# arduinoShield.net
KiCad netlist of a schematic drawn in EAGLE
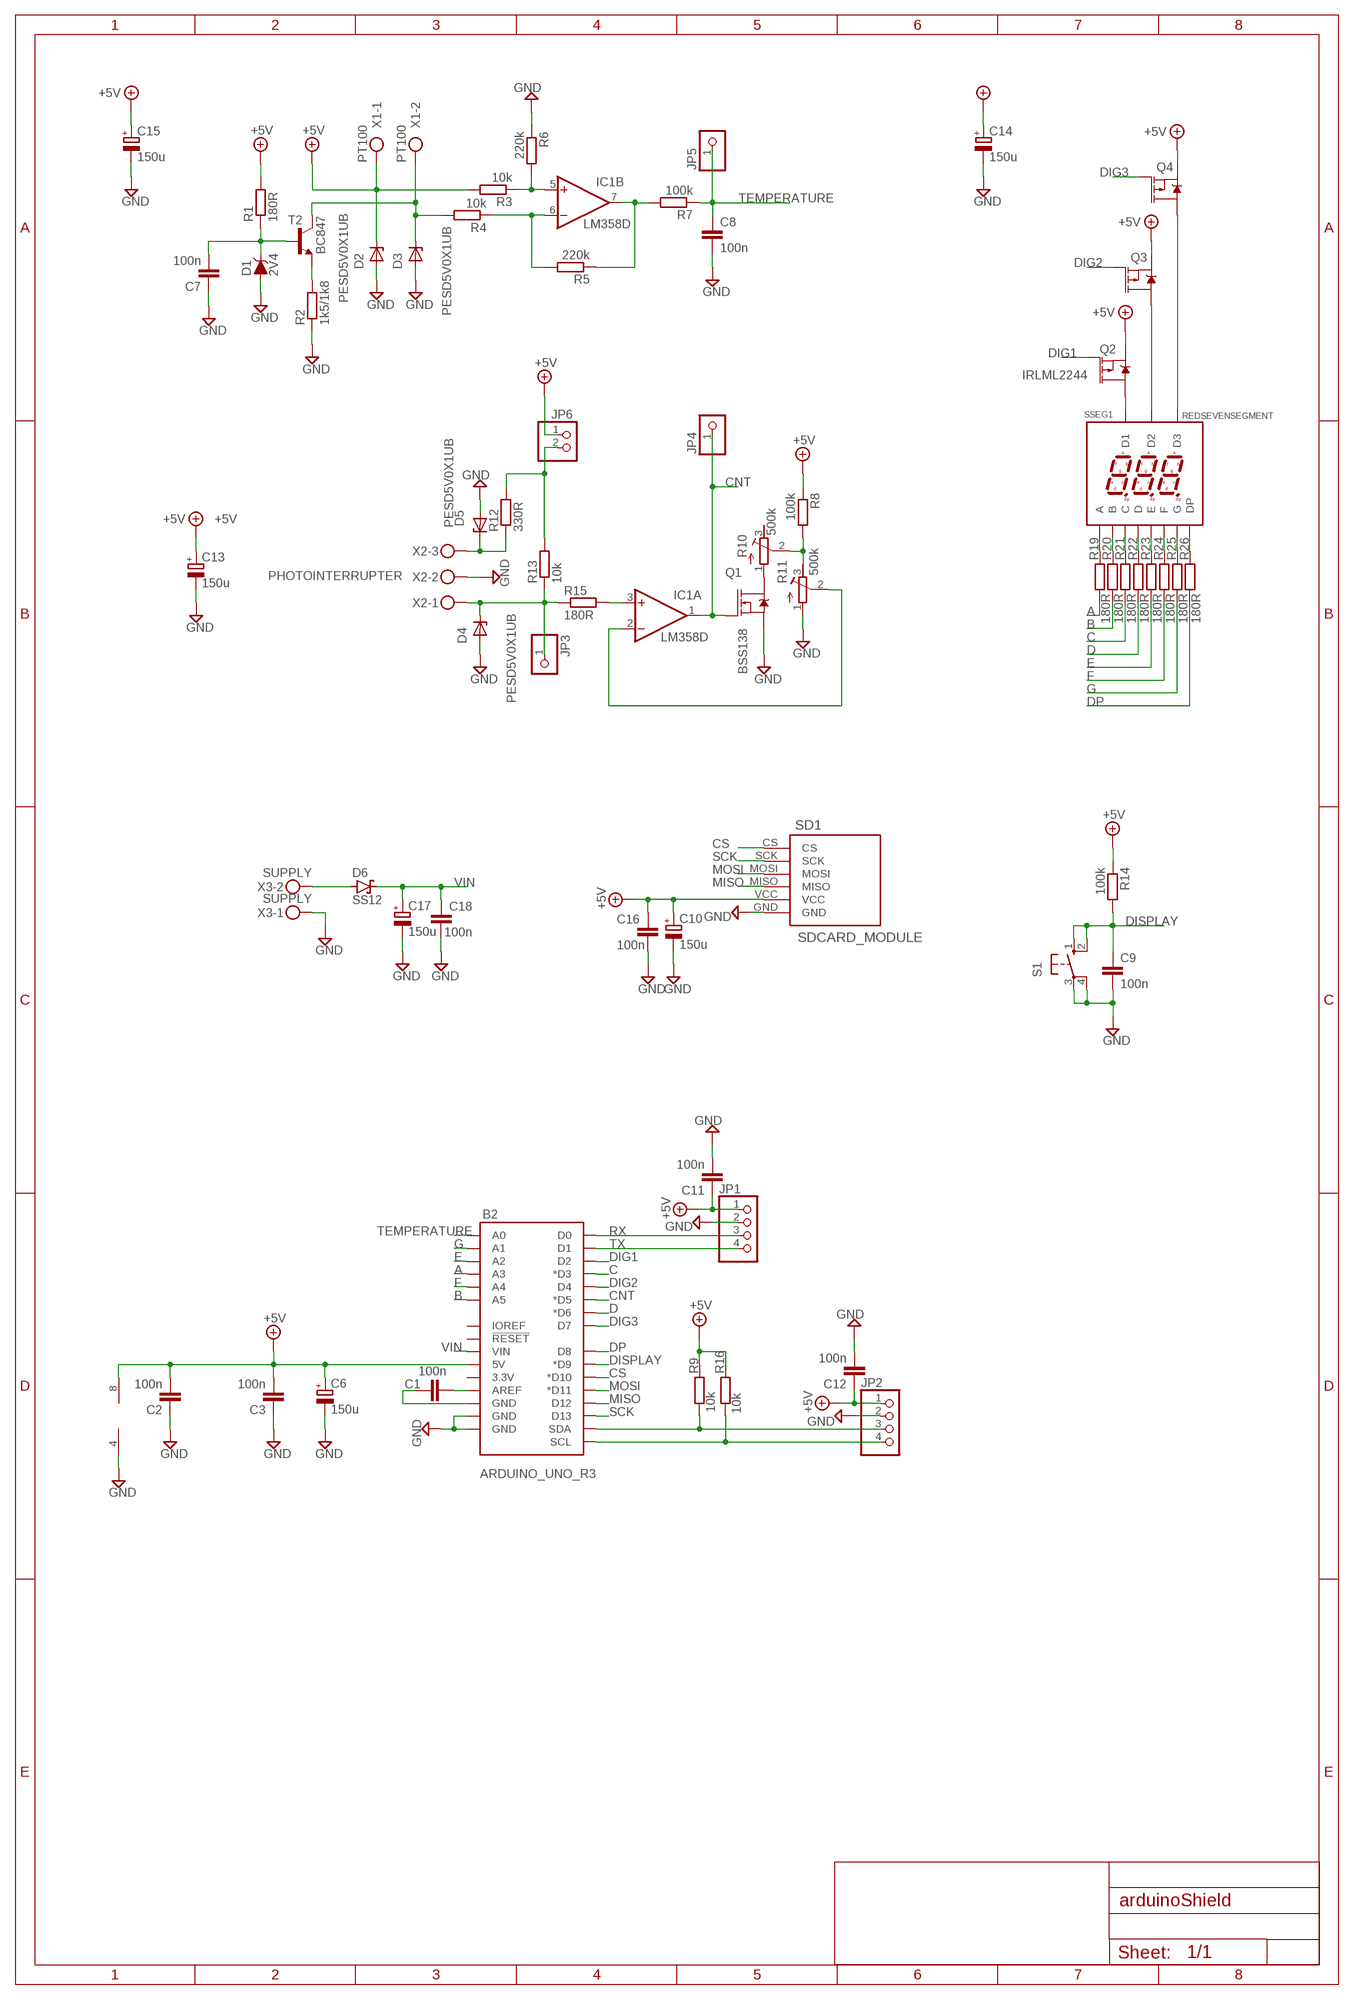
[diagram p0: schematic, sheet 1]

(export (version "E")
  (design (tool "Eeschema 10.0.6"))
  (components
    (comp (ref "B2")
      (value "ARDUINO_UNO_R3")
      (footprint "eagle-import:ARDUINO_R3_NOISP")
      (libsource (lib "eagle-import") (part "ARDUINO_UNO_R3_HOLES_NOISP"))
    )
    (comp (ref "C1")
      (value "100n")
      (footprint "eagle-import:C0805")
      (libsource (lib "eagle-import") (part "C-EUC0805"))
    )
    (comp (ref "C2")
      (value "100n")
      (footprint "eagle-import:C0805")
      (libsource (lib "eagle-import") (part "C-EUC0805"))
    )
    (comp (ref "C3")
      (value "100n")
      (footprint "eagle-import:C0805")
      (libsource (lib "eagle-import") (part "C-EUC0805"))
    )
    (comp (ref "C6")
      (value "150u")
      (footprint "eagle-import:D_7343-31R")
      (libsource (lib "eagle-import") (part "CPOL-EUD/7343-31R"))
    )
    (comp (ref "C7")
      (value "100n")
      (footprint "eagle-import:C0805")
      (libsource (lib "eagle-import") (part "C-EUC0805"))
    )
    (comp (ref "C8")
      (value "100n")
      (footprint "eagle-import:C0805")
      (libsource (lib "eagle-import") (part "C-EUC0805"))
    )
    (comp (ref "C9")
      (value "100n")
      (footprint "eagle-import:C0805")
      (libsource (lib "eagle-import") (part "C-EUC0805"))
    )
    (comp (ref "C10")
      (value "150u")
      (footprint "eagle-import:D_7343-31R")
      (libsource (lib "eagle-import") (part "CPOL-EUD/7343-31R"))
    )
    (comp (ref "C11")
      (value "100n")
      (footprint "eagle-import:C0805")
      (libsource (lib "eagle-import") (part "C-EUC0805"))
    )
    (comp (ref "C12")
      (value "100n")
      (footprint "eagle-import:C0805")
      (libsource (lib "eagle-import") (part "C-EUC0805"))
    )
    (comp (ref "C13")
      (value "150u")
      (footprint "eagle-import:D_7343-31R")
      (libsource (lib "eagle-import") (part "CPOL-EUD/7343-31R"))
    )
    (comp (ref "C14")
      (value "150u")
      (footprint "eagle-import:D_7343-31R")
      (libsource (lib "eagle-import") (part "CPOL-EUD/7343-31R"))
    )
    (comp (ref "C15")
      (value "150u")
      (footprint "eagle-import:D_7343-31R")
      (libsource (lib "eagle-import") (part "CPOL-EUD/7343-31R"))
    )
    (comp (ref "C16")
      (value "100n")
      (footprint "eagle-import:C0805")
      (libsource (lib "eagle-import") (part "C-EUC0805"))
    )
    (comp (ref "C17")
      (value "150u")
      (footprint "eagle-import:D_7343-31R")
      (libsource (lib "eagle-import") (part "CPOL-EUD/7343-31R"))
    )
    (comp (ref "C18")
      (value "100n")
      (footprint "eagle-import:C0805")
      (libsource (lib "eagle-import") (part "C-EUC0805"))
    )
    (comp (ref "D1")
      (value "2V4")
      (footprint "eagle-import:SOD-323")
      (libsource (lib "eagle-import") (part "DIODE-ZENER-BZT52C3V6S"))
    )
    (comp (ref "D2")
      (value "PESD5V0X1UB")
      (footprint "eagle-import:SOD523")
      (libsource (lib "eagle-import") (part "PESD5V0X1UB"))
    )
    (comp (ref "D3")
      (value "PESD5V0X1UB")
      (footprint "eagle-import:SOD523")
      (libsource (lib "eagle-import") (part "PESD5V0X1UB"))
    )
    (comp (ref "D4")
      (value "PESD5V0X1UB")
      (footprint "eagle-import:SOD523")
      (libsource (lib "eagle-import") (part "PESD5V0X1UB"))
    )
    (comp (ref "D5")
      (value "PESD5V0X1UB")
      (footprint "eagle-import:SOD523")
      (libsource (lib "eagle-import") (part "PESD5V0X1UB"))
    )
    (comp (ref "D6")
      (value "SS12")
      (footprint "eagle-import:SMA")
      (fields
        (field (name "DIGIKEY_PART_NUMBER") "SS12FSCT-ND")
        (field (name "MANUFACTURER") "ON Semiconductor")
        (field (name "CREATED_BY") "PCBLayout.com")
      )
      (libsource (lib "eagle-import") (part "SS12"))
    )
    (comp (ref "IC1")
      (value "LM358D")
      (footprint "eagle-import:SO08")
      (libsource (lib "eagle-import") (part "LM358D"))
    )
    (comp (ref "JP1")
      (value "PINHD-1X4")
      (footprint "eagle-import:1X04")
      (libsource (lib "eagle-import") (part "PINHD-1X4"))
    )
    (comp (ref "JP2")
      (value "PINHD-1X4")
      (footprint "eagle-import:1X04")
      (libsource (lib "eagle-import") (part "PINHD-1X4"))
    )
    (comp (ref "JP3")
      (value "PINHD-1X1")
      (footprint "eagle-import:1X01")
      (libsource (lib "eagle-import") (part "PINHD-1X1"))
    )
    (comp (ref "JP4")
      (value "PINHD-1X1")
      (footprint "eagle-import:1X01")
      (libsource (lib "eagle-import") (part "PINHD-1X1"))
    )
    (comp (ref "JP5")
      (value "PINHD-1X1")
      (footprint "eagle-import:1X01")
      (libsource (lib "eagle-import") (part "PINHD-1X1"))
    )
    (comp (ref "JP6")
      (value "PINHD-1X2")
      (footprint "eagle-import:1X02")
      (libsource (lib "eagle-import") (part "PINHD-1X2"))
    )
    (comp (ref "Q1")
      (value "BSS138")
      (footprint "eagle-import:SOT23-3")
      (libsource (lib "eagle-import") (part "MOSFET-NCH-BSS138"))
    )
    (comp (ref "Q2")
      (value "IRLML2244")
      (footprint "eagle-import:SOT23-3")
      (libsource (lib "eagle-import") (part "MOSFET_PCH-IRLML2244"))
    )
    (comp (ref "Q3")
      (value "4.3A/20V/54mΩ")
      (footprint "eagle-import:SOT23-3")
      (libsource (lib "eagle-import") (part "MOSFET_PCH-IRLML2244"))
    )
    (comp (ref "Q4")
      (value "4.3A/20V/54mΩ")
      (footprint "eagle-import:SOT23-3")
      (libsource (lib "eagle-import") (part "MOSFET_PCH-IRLML2244"))
    )
    (comp (ref "R1")
      (value "180R")
      (footprint "eagle-import:R0805")
      (libsource (lib "eagle-import") (part "R-EU_R0805"))
    )
    (comp (ref "R2")
      (value "1k5/1k8")
      (footprint "eagle-import:R0805")
      (libsource (lib "eagle-import") (part "R-EU_R0805"))
    )
    (comp (ref "R3")
      (value "10k")
      (footprint "eagle-import:R0805")
      (libsource (lib "eagle-import") (part "R-EU_R0805"))
    )
    (comp (ref "R4")
      (value "10k")
      (footprint "eagle-import:R0805")
      (libsource (lib "eagle-import") (part "R-EU_R0805"))
    )
    (comp (ref "R5")
      (value "220k")
      (footprint "eagle-import:R0805")
      (libsource (lib "eagle-import") (part "R-EU_R0805"))
    )
    (comp (ref "R6")
      (value "220k")
      (footprint "eagle-import:R0805")
      (libsource (lib "eagle-import") (part "R-EU_R0805"))
    )
    (comp (ref "R7")
      (value "100k")
      (footprint "eagle-import:R0805")
      (libsource (lib "eagle-import") (part "R-EU_R0805"))
    )
    (comp (ref "R8")
      (value "100k")
      (footprint "eagle-import:R0805")
      (libsource (lib "eagle-import") (part "R-EU_R0805"))
    )
    (comp (ref "R9")
      (value "10k")
      (footprint "eagle-import:R0805")
      (libsource (lib "eagle-import") (part "R-EU_R0805"))
    )
    (comp (ref "R10")
      (value "500k")
      (footprint "eagle-import:RTRIM64Y")
      (libsource (lib "eagle-import") (part "R-TRIMM64Y"))
    )
    (comp (ref "R11")
      (value "500k")
      (footprint "eagle-import:RTRIM64Y")
      (libsource (lib "eagle-import") (part "R-TRIMM64Y"))
    )
    (comp (ref "R12")
      (value "330R")
      (footprint "eagle-import:R0805")
      (libsource (lib "eagle-import") (part "R-EU_R0805"))
    )
    (comp (ref "R13")
      (value "10k")
      (footprint "eagle-import:R0805")
      (libsource (lib "eagle-import") (part "R-EU_R0805"))
    )
    (comp (ref "R14")
      (value "100k")
      (footprint "eagle-import:R0805")
      (libsource (lib "eagle-import") (part "R-EU_R0805"))
    )
    (comp (ref "R15")
      (value "180R")
      (footprint "eagle-import:R0805")
      (libsource (lib "eagle-import") (part "R-EU_R0805"))
    )
    (comp (ref "R16")
      (value "10k")
      (footprint "eagle-import:R0805")
      (libsource (lib "eagle-import") (part "R-EU_R0805"))
    )
    (comp (ref "R19")
      (value "180R")
      (footprint "eagle-import:R0805")
      (libsource (lib "eagle-import") (part "R-EU_R0805"))
    )
    (comp (ref "R20")
      (value "180R")
      (footprint "eagle-import:R0805")
      (libsource (lib "eagle-import") (part "R-EU_R0805"))
    )
    (comp (ref "R21")
      (value "180R")
      (footprint "eagle-import:R0805")
      (libsource (lib "eagle-import") (part "R-EU_R0805"))
    )
    (comp (ref "R22")
      (value "180R")
      (footprint "eagle-import:R0805")
      (libsource (lib "eagle-import") (part "R-EU_R0805"))
    )
    (comp (ref "R23")
      (value "180R")
      (footprint "eagle-import:R0805")
      (libsource (lib "eagle-import") (part "R-EU_R0805"))
    )
    (comp (ref "R24")
      (value "180R")
      (footprint "eagle-import:R0805")
      (libsource (lib "eagle-import") (part "R-EU_R0805"))
    )
    (comp (ref "R25")
      (value "180R")
      (footprint "eagle-import:R0805")
      (libsource (lib "eagle-import") (part "R-EU_R0805"))
    )
    (comp (ref "R26")
      (value "180R")
      (footprint "eagle-import:R0805")
      (libsource (lib "eagle-import") (part "R-EU_R0805"))
    )
    (comp (ref "S1")
      (value "10-XX")
      (footprint "eagle-import:B3F-10XX")
      (fields (field (name "MPN") "B3F-1000"))
      (libsource (lib "eagle-import") (part "10-XX"))
    )
    (comp (ref "SD1")
      (value "SDCARD_MODULE")
      (footprint "eagle-import:SD_MODULE")
      (libsource (lib "eagle-import") (part "SDCARD_MODULE"))
    )
    (comp (ref "SSEG1")
      (value "REDSEVENSEGMENT")
      (footprint "eagle-import:REDSEVENSEGMENT")
      (libsource (lib "eagle-import") (part "REDSEVENSEGMENT"))
    )
    (comp (ref "T2")
      (value "BC847")
      (footprint "eagle-import:SOT23-BEC")
      (libsource (lib "eagle-import") (part "-NPN-SOT23-BECBC847"))
    )
    (comp (ref "X1")
      (value "PT100")
      (footprint "eagle-import:2_2.54MM")
      (libsource (lib "eagle-import") (part "PCB2_TERMINAL-BLOCK"))
    )
    (comp (ref "X2")
      (value "PHOTOINTERRUPTER")
      (footprint "eagle-import:MKDSN1,5_3-5,08")
      (libsource (lib "eagle-import") (part "MKDSN1,5/3-5,08"))
    )
    (comp (ref "X3")
      (value "SUPPLY")
      (footprint "eagle-import:MKDSN1,5_2-5,08")
      (libsource (lib "eagle-import") (part "MKDSN1,5/2-5,08"))
    )
  )
  (nets
    (net (code "1") (name "+5V") (class "Default")
      (node (ref "B2") (pin "5V") (pinfunction "5V_5V") (pintype "bidirectional"))
      (node (ref "C10") (pin "+") (pinfunction "+_+") (pintype "passive"))
      (node (ref "C11") (pin "1") (pinfunction "1_1") (pintype "passive"))
      (node (ref "C12") (pin "1") (pinfunction "1_1") (pintype "passive"))
      (node (ref "C13") (pin "+") (pinfunction "+_+") (pintype "passive"))
      (node (ref "C14") (pin "+") (pinfunction "+_+") (pintype "passive"))
      (node (ref "C15") (pin "+") (pinfunction "+_+") (pintype "passive"))
      (node (ref "C16") (pin "1") (pinfunction "1_1") (pintype "passive"))
      (node (ref "C2") (pin "2") (pinfunction "2_2") (pintype "passive"))
      (node (ref "C3") (pin "2") (pinfunction "2_2") (pintype "passive"))
      (node (ref "C6") (pin "+") (pinfunction "+_+") (pintype "passive"))
      (node (ref "D2") (pin "1") (pinfunction "K_1") (pintype "passive"))
      (node (ref "IC1") (pin "8") (pinfunction "V+_8") (pintype "power_in"))
      (node (ref "JP1") (pin "1") (pinfunction "1_1") (pintype "passive"))
      (node (ref "JP2") (pin "1") (pinfunction "1_1") (pintype "passive"))
      (node (ref "JP6") (pin "1") (pinfunction "1_1") (pintype "passive"))
      (node (ref "Q2") (pin "2") (pinfunction "S_2") (pintype "bidirectional"))
      (node (ref "Q3") (pin "2") (pinfunction "S_2") (pintype "bidirectional"))
      (node (ref "Q4") (pin "2") (pinfunction "S_2") (pintype "bidirectional"))
      (node (ref "R1") (pin "2") (pinfunction "2_2") (pintype "passive"))
      (node (ref "R14") (pin "1") (pinfunction "1_1") (pintype "passive"))
      (node (ref "R16") (pin "2") (pinfunction "2_2") (pintype "passive"))
      (node (ref "R3") (pin "2") (pinfunction "2_2") (pintype "passive"))
      (node (ref "R8") (pin "1") (pinfunction "1_1") (pintype "passive"))
      (node (ref "R9") (pin "2") (pinfunction "2_2") (pintype "passive"))
      (node (ref "SD1") (pin "VCC") (pinfunction "VCC_VCC") (pintype "bidirectional"))
      (node (ref "X1") (pin "1") (pinfunction "KL_1") (pintype "passive"))
    )
    (net (code "2") (name "/A") (class "Default")
      (node (ref "B2") (pin "A3") (pinfunction "A3_A3") (pintype "bidirectional"))
      (node (ref "R19") (pin "1") (pinfunction "1_1") (pintype "passive"))
    )
    (net (code "3") (name "/B") (class "Default")
      (node (ref "B2") (pin "A5") (pinfunction "A5_A5") (pintype "bidirectional"))
      (node (ref "R20") (pin "1") (pinfunction "1_1") (pintype "passive"))
    )
    (net (code "4") (name "/C") (class "Default")
      (node (ref "B2") (pin "D3") (pinfunction "*D3_D3") (pintype "bidirectional"))
      (node (ref "R21") (pin "1") (pinfunction "1_1") (pintype "passive"))
    )
    (net (code "5") (name "/CNT") (class "Default")
      (node (ref "B2") (pin "D5") (pinfunction "*D5_D5") (pintype "bidirectional"))
      (node (ref "IC1") (pin "1") (pinfunction "OUT_1") (pintype "output"))
      (node (ref "JP4") (pin "1") (pinfunction "1_1") (pintype "passive"))
      (node (ref "Q1") (pin "1") (pinfunction "G_1") (pintype "bidirectional"))
    )
    (net (code "6") (name "/CS") (class "Default")
      (node (ref "B2") (pin "D10") (pinfunction "*D10_D10") (pintype "bidirectional"))
      (node (ref "SD1") (pin "CS") (pinfunction "CS_CS") (pintype "bidirectional"))
    )
    (net (code "7") (name "/D") (class "Default")
      (node (ref "B2") (pin "D6") (pinfunction "*D6_D6") (pintype "bidirectional"))
      (node (ref "R22") (pin "1") (pinfunction "1_1") (pintype "passive"))
    )
    (net (code "8") (name "/DIG1") (class "Default")
      (node (ref "B2") (pin "D2") (pinfunction "D2_D2") (pintype "bidirectional"))
      (node (ref "Q2") (pin "1") (pinfunction "G_1") (pintype "bidirectional"))
    )
    (net (code "9") (name "/DIG2") (class "Default")
      (node (ref "B2") (pin "D4") (pinfunction "D4_D4") (pintype "bidirectional"))
      (node (ref "Q3") (pin "1") (pinfunction "G_1") (pintype "bidirectional"))
    )
    (net (code "10") (name "/DIG3") (class "Default")
      (node (ref "B2") (pin "D7") (pinfunction "D7_D7") (pintype "bidirectional"))
      (node (ref "Q4") (pin "1") (pinfunction "G_1") (pintype "bidirectional"))
    )
    (net (code "11") (name "/DISPLAY") (class "Default")
      (node (ref "B2") (pin "D9") (pinfunction "*D9_D9") (pintype "bidirectional"))
      (node (ref "C9") (pin "1") (pinfunction "1_1") (pintype "passive"))
      (node (ref "R14") (pin "2") (pinfunction "2_2") (pintype "passive"))
      (node (ref "S1") (pin "1") (pinfunction "S_1") (pintype "passive"))
      (node (ref "S1") (pin "2") (pinfunction "S1_2") (pintype "passive"))
    )
    (net (code "12") (name "/DP") (class "Default")
      (node (ref "B2") (pin "D8") (pinfunction "D8_D8") (pintype "bidirectional"))
      (node (ref "R26") (pin "1") (pinfunction "1_1") (pintype "passive"))
    )
    (net (code "13") (name "/E") (class "Default")
      (node (ref "B2") (pin "A2") (pinfunction "A2_A2") (pintype "bidirectional"))
      (node (ref "R23") (pin "1") (pinfunction "1_1") (pintype "passive"))
    )
    (net (code "14") (name "/F") (class "Default")
      (node (ref "B2") (pin "A4") (pinfunction "A4_A4") (pintype "bidirectional"))
      (node (ref "R24") (pin "1") (pinfunction "1_1") (pintype "passive"))
    )
    (net (code "15") (name "/G") (class "Default")
      (node (ref "B2") (pin "A1") (pinfunction "A1_A1") (pintype "bidirectional"))
      (node (ref "R25") (pin "1") (pinfunction "1_1") (pintype "passive"))
    )
    (net (code "16") (name "/MISO") (class "Default")
      (node (ref "B2") (pin "D12") (pinfunction "D12_D12") (pintype "bidirectional"))
      (node (ref "SD1") (pin "MISO") (pinfunction "MISO_MISO") (pintype "bidirectional"))
    )
    (net (code "17") (name "/MOSI") (class "Default")
      (node (ref "B2") (pin "D11") (pinfunction "*D11_D11") (pintype "bidirectional"))
      (node (ref "SD1") (pin "MOSI") (pinfunction "MOSI_MOSI") (pintype "bidirectional"))
    )
    (net (code "18") (name "/RX") (class "Default")
      (node (ref "B2") (pin "D0") (pinfunction "D0_D0") (pintype "bidirectional"))
      (node (ref "JP1") (pin "3") (pinfunction "3_3") (pintype "passive"))
    )
    (net (code "19") (name "/SCK") (class "Default")
      (node (ref "B2") (pin "D13") (pinfunction "D13_D13") (pintype "bidirectional"))
      (node (ref "SD1") (pin "SCK") (pinfunction "SCK_SCK") (pintype "bidirectional"))
    )
    (net (code "20") (name "/TEMPERATURE") (class "Default")
      (node (ref "B2") (pin "A0") (pinfunction "A0_A0") (pintype "bidirectional"))
      (node (ref "C8") (pin "1") (pinfunction "1_1") (pintype "passive"))
      (node (ref "JP5") (pin "1") (pinfunction "1_1") (pintype "passive"))
      (node (ref "R7") (pin "1") (pinfunction "1_1") (pintype "passive"))
    )
    (net (code "21") (name "/TX") (class "Default")
      (node (ref "B2") (pin "D1") (pinfunction "D1_D1") (pintype "bidirectional"))
      (node (ref "JP1") (pin "4") (pinfunction "4_4") (pintype "passive"))
    )
    (net (code "22") (name "/VIN") (class "Default")
      (node (ref "B2") (pin "VIN") (pinfunction "VIN_VIN") (pintype "bidirectional"))
      (node (ref "C17") (pin "+") (pinfunction "+_+") (pintype "passive"))
      (node (ref "C18") (pin "2") (pinfunction "2_2") (pintype "passive"))
      (node (ref "D6") (pin "C") (pinfunction "C_C") (pintype "passive"))
    )
    (net (code "23") (name "GND") (class "Default")
      (node (ref "B2") (pin "GND@1") (pinfunction "GND_GND@1") (pintype "bidirectional"))
      (node (ref "B2") (pin "GND@2") (pinfunction "GND_GND@2") (pintype "bidirectional"))
      (node (ref "C10") (pin "-") (pinfunction "-_-") (pintype "passive"))
      (node (ref "C11") (pin "2") (pinfunction "2_2") (pintype "passive"))
      (node (ref "C12") (pin "2") (pinfunction "2_2") (pintype "passive"))
      (node (ref "C13") (pin "-") (pinfunction "-_-") (pintype "passive"))
      (node (ref "C14") (pin "-") (pinfunction "-_-") (pintype "passive"))
      (node (ref "C15") (pin "-") (pinfunction "-_-") (pintype "passive"))
      (node (ref "C16") (pin "2") (pinfunction "2_2") (pintype "passive"))
      (node (ref "C17") (pin "-") (pinfunction "-_-") (pintype "passive"))
      (node (ref "C18") (pin "1") (pinfunction "1_1") (pintype "passive"))
      (node (ref "C2") (pin "1") (pinfunction "1_1") (pintype "passive"))
      (node (ref "C3") (pin "1") (pinfunction "1_1") (pintype "passive"))
      (node (ref "C6") (pin "-") (pinfunction "-_-") (pintype "passive"))
      (node (ref "C7") (pin "1") (pinfunction "1_1") (pintype "passive"))
      (node (ref "C8") (pin "2") (pinfunction "2_2") (pintype "passive"))
      (node (ref "C9") (pin "2") (pinfunction "2_2") (pintype "passive"))
      (node (ref "D1") (pin "A") (pinfunction "A_A") (pintype "passive"))
      (node (ref "D2") (pin "2") (pinfunction "A_2") (pintype "passive"))
      (node (ref "D3") (pin "2") (pinfunction "A_2") (pintype "passive"))
      (node (ref "D4") (pin "2") (pinfunction "A_2") (pintype "passive"))
      (node (ref "D5") (pin "2") (pinfunction "A_2") (pintype "passive"))
      (node (ref "IC1") (pin "4") (pinfunction "V-_4") (pintype "power_in"))
      (node (ref "JP1") (pin "2") (pinfunction "2_2") (pintype "passive"))
      (node (ref "JP2") (pin "2") (pinfunction "2_2") (pintype "passive"))
      (node (ref "Q1") (pin "2") (pinfunction "S_2") (pintype "bidirectional"))
      (node (ref "R11") (pin "1") (pinfunction "A_1") (pintype "passive"))
      (node (ref "R2") (pin "1") (pinfunction "1_1") (pintype "passive"))
      (node (ref "R6") (pin "1") (pinfunction "1_1") (pintype "passive"))
      (node (ref "S1") (pin "3") (pinfunction "P_3") (pintype "passive"))
      (node (ref "S1") (pin "4") (pinfunction "P1_4") (pintype "passive"))
      (node (ref "SD1") (pin "GND") (pinfunction "GND_GND") (pintype "bidirectional"))
      (node (ref "X2") (pin "2") (pinfunction "KL_2") (pintype "passive"))
      (node (ref "X3") (pin "1") (pinfunction "KL_1") (pintype "passive"))
    )
    (net (code "24") (name "Net-(B2-GND-PadGND@3)") (class "Default")
      (node (ref "B2") (pin "GND@3") (pinfunction "GND_GND@3") (pintype "bidirectional"))
      (node (ref "C1") (pin "1") (pinfunction "1_1") (pintype "passive"))
    )
    (net (code "25") (name "Net-(B2-PadAREF)") (class "Default")
      (node (ref "B2") (pin "AREF") (pinfunction "AREF_AREF") (pintype "bidirectional"))
      (node (ref "C1") (pin "2") (pinfunction "2_2") (pintype "passive"))
    )
    (net (code "26") (name "Net-(B2-PadSCL)") (class "Default")
      (node (ref "B2") (pin "SCL") (pinfunction "SCL_SCL") (pintype "bidirectional"))
      (node (ref "JP2") (pin "4") (pinfunction "4_4") (pintype "passive"))
      (node (ref "R16") (pin "1") (pinfunction "1_1") (pintype "passive"))
    )
    (net (code "27") (name "Net-(B2-PadSDA)") (class "Default")
      (node (ref "B2") (pin "SDA") (pinfunction "SDA_SDA") (pintype "bidirectional"))
      (node (ref "JP2") (pin "3") (pinfunction "3_3") (pintype "passive"))
      (node (ref "R9") (pin "1") (pinfunction "1_1") (pintype "passive"))
    )
    (net (code "28") (name "Net-(C7-Pad2)") (class "Default")
      (node (ref "C7") (pin "2") (pinfunction "2_2") (pintype "passive"))
      (node (ref "D1") (pin "C") (pinfunction "C_C") (pintype "passive"))
      (node (ref "R1") (pin "1") (pinfunction "1_1") (pintype "passive"))
      (node (ref "T2") (pin "B") (pinfunction "B_B") (pintype "passive"))
    )
    (net (code "29") (name "Net-(D3-K)") (class "Default")
      (node (ref "D3") (pin "1") (pinfunction "K_1") (pintype "passive"))
      (node (ref "R4") (pin "2") (pinfunction "2_2") (pintype "passive"))
      (node (ref "T2") (pin "C") (pinfunction "C_C") (pintype "passive"))
      (node (ref "X1") (pin "2") (pinfunction "KL_2") (pintype "passive"))
    )
    (net (code "30") (name "Net-(D4-K)") (class "Default")
      (node (ref "D4") (pin "1") (pinfunction "K_1") (pintype "passive"))
      (node (ref "JP3") (pin "1") (pinfunction "1_1") (pintype "passive"))
      (node (ref "R13") (pin "1") (pinfunction "1_1") (pintype "passive"))
      (node (ref "R15") (pin "1") (pinfunction "1_1") (pintype "passive"))
      (node (ref "X2") (pin "1") (pinfunction "KL_1") (pintype "passive"))
    )
    (net (code "31") (name "Net-(D5-K)") (class "Default")
      (node (ref "D5") (pin "1") (pinfunction "K_1") (pintype "passive"))
      (node (ref "R12") (pin "1") (pinfunction "1_1") (pintype "passive"))
      (node (ref "X2") (pin "3") (pinfunction "KL_3") (pintype "passive"))
    )
    (net (code "32") (name "Net-(IC1A-+IN)") (class "Default")
      (node (ref "IC1") (pin "3") (pinfunction "+IN_3") (pintype "input"))
      (node (ref "R15") (pin "2") (pinfunction "2_2") (pintype "passive"))
    )
    (net (code "33") (name "Net-(IC1A--IN)") (class "Default")
      (node (ref "IC1") (pin "2") (pinfunction "-IN_2") (pintype "input"))
      (node (ref "R11") (pin "2") (pinfunction "S_2") (pintype "passive"))
    )
    (net (code "34") (name "Net-(IC1B-+IN)") (class "Default")
      (node (ref "IC1") (pin "5") (pinfunction "+IN_5") (pintype "input"))
      (node (ref "R3") (pin "1") (pinfunction "1_1") (pintype "passive"))
      (node (ref "R6") (pin "2") (pinfunction "2_2") (pintype "passive"))
    )
    (net (code "35") (name "Net-(IC1B--IN)") (class "Default")
      (node (ref "IC1") (pin "6") (pinfunction "-IN_6") (pintype "input"))
      (node (ref "R4") (pin "1") (pinfunction "1_1") (pintype "passive"))
      (node (ref "R5") (pin "2") (pinfunction "2_2") (pintype "passive"))
    )
    (net (code "36") (name "Net-(IC1B-OUT)") (class "Default")
      (node (ref "IC1") (pin "7") (pinfunction "OUT_7") (pintype "output"))
      (node (ref "R5") (pin "1") (pinfunction "1_1") (pintype "passive"))
      (node (ref "R7") (pin "2") (pinfunction "2_2") (pintype "passive"))
    )
    (net (code "37") (name "Net-(JP6-Pad2)") (class "Default")
      (node (ref "JP6") (pin "2") (pinfunction "2_2") (pintype "passive"))
      (node (ref "R12") (pin "2") (pinfunction "2_2") (pintype "passive"))
      (node (ref "R13") (pin "2") (pinfunction "2_2") (pintype "passive"))
    )
    (net (code "38") (name "Net-(Q1-D)") (class "Default")
      (node (ref "Q1") (pin "3") (pinfunction "D_3") (pintype "bidirectional"))
      (node (ref "R10") (pin "1") (pinfunction "A_1") (pintype "passive"))
    )
    (net (code "39") (name "Net-(Q2-D)") (class "Default")
      (node (ref "Q2") (pin "3") (pinfunction "D_3") (pintype "bidirectional"))
      (node (ref "SSEG1") (pin "2") (pinfunction "D1_2") (pintype "bidirectional"))
    )
    (net (code "40") (name "Net-(Q3-D)") (class "Default")
      (node (ref "Q3") (pin "3") (pinfunction "D_3") (pintype "bidirectional"))
      (node (ref "SSEG1") (pin "4") (pinfunction "D2_4") (pintype "bidirectional"))
    )
    (net (code "41") (name "Net-(Q4-D)") (class "Default")
      (node (ref "Q4") (pin "3") (pinfunction "D_3") (pintype "bidirectional"))
      (node (ref "SSEG1") (pin "5") (pinfunction "D3_5") (pintype "bidirectional"))
    )
    (net (code "42") (name "Net-(R2-Pad2)") (class "Default")
      (node (ref "R2") (pin "2") (pinfunction "2_2") (pintype "passive"))
      (node (ref "T2") (pin "E") (pinfunction "E_E") (pintype "passive"))
    )
    (net (code "43") (name "Net-(R10-S)") (class "Default")
      (node (ref "R10") (pin "2") (pinfunction "S_2") (pintype "passive"))
      (node (ref "R11") (pin "3") (pinfunction "E_3") (pintype "passive"))
      (node (ref "R8") (pin "2") (pinfunction "2_2") (pintype "passive"))
    )
    (net (code "44") (name "Net-(SSEG1-A)") (class "Default")
      (node (ref "R19") (pin "2") (pinfunction "2_2") (pintype "passive"))
      (node (ref "SSEG1") (pin "9") (pinfunction "A_9") (pintype "bidirectional"))
    )
    (net (code "45") (name "Net-(SSEG1-B)") (class "Default")
      (node (ref "R20") (pin "2") (pinfunction "2_2") (pintype "passive"))
      (node (ref "SSEG1") (pin "7") (pinfunction "B_7") (pintype "bidirectional"))
    )
    (net (code "46") (name "Net-(SSEG1-C)") (class "Default")
      (node (ref "R21") (pin "2") (pinfunction "2_2") (pintype "passive"))
      (node (ref "SSEG1") (pin "1") (pinfunction "C_1") (pintype "bidirectional"))
    )
    (net (code "47") (name "Net-(SSEG1-D)") (class "Default")
      (node (ref "R22") (pin "2") (pinfunction "2_2") (pintype "passive"))
      (node (ref "SSEG1") (pin "3") (pinfunction "D_3") (pintype "bidirectional"))
    )
    (net (code "48") (name "Net-(SSEG1-DP)") (class "Default")
      (node (ref "R26") (pin "2") (pinfunction "2_2") (pintype "passive"))
      (node (ref "SSEG1") (pin "6") (pinfunction "DP_6") (pintype "bidirectional"))
    )
    (net (code "49") (name "Net-(SSEG1-E)") (class "Default")
      (node (ref "R23") (pin "2") (pinfunction "2_2") (pintype "passive"))
      (node (ref "SSEG1") (pin "10") (pinfunction "E_10") (pintype "bidirectional"))
    )
    (net (code "50") (name "Net-(SSEG1-F)") (class "Default")
      (node (ref "R24") (pin "2") (pinfunction "2_2") (pintype "passive"))
      (node (ref "SSEG1") (pin "8") (pinfunction "F_8") (pintype "bidirectional"))
    )
    (net (code "51") (name "Net-(SSEG1-G)") (class "Default")
      (node (ref "R25") (pin "2") (pinfunction "2_2") (pintype "passive"))
      (node (ref "SSEG1") (pin "11") (pinfunction "G_11") (pintype "bidirectional"))
    )
    (net (code "52") (name "Net-(X3B-KL)") (class "Default")
      (node (ref "D6") (pin "A") (pinfunction "A_A") (pintype "passive"))
      (node (ref "X3") (pin "2") (pinfunction "KL_2") (pintype "passive"))
    )
    (net (code "53") (name "unconnected-(B2-Pad3.3V)") (class "Default")
      (node (ref "B2") (pin "3.3V") (pinfunction "3.3V_3.3V") (pintype "bidirectional"))
    )
    (net (code "54") (name "unconnected-(B2-PadIOREF)") (class "Default")
      (node (ref "B2") (pin "IOREF") (pinfunction "IOREF_IOREF") (pintype "bidirectional"))
    )
    (net (code "55") (name "unconnected-(B2-~{RESET}-PadRESET@1)") (class "Default")
      (node (ref "B2") (pin "RESET@1") (pinfunction "~{RESET}_RESET@1") (pintype "bidirectional"))
    )
    (net (code "56") (name "unconnected-(R10-E-Pad3)") (class "Default")
      (node (ref "R10") (pin "3") (pinfunction "E_3") (pintype "passive"))
    )
  )
)
